# FPGA.net
KiCad netlist of a schematic drawn in Altium Designer
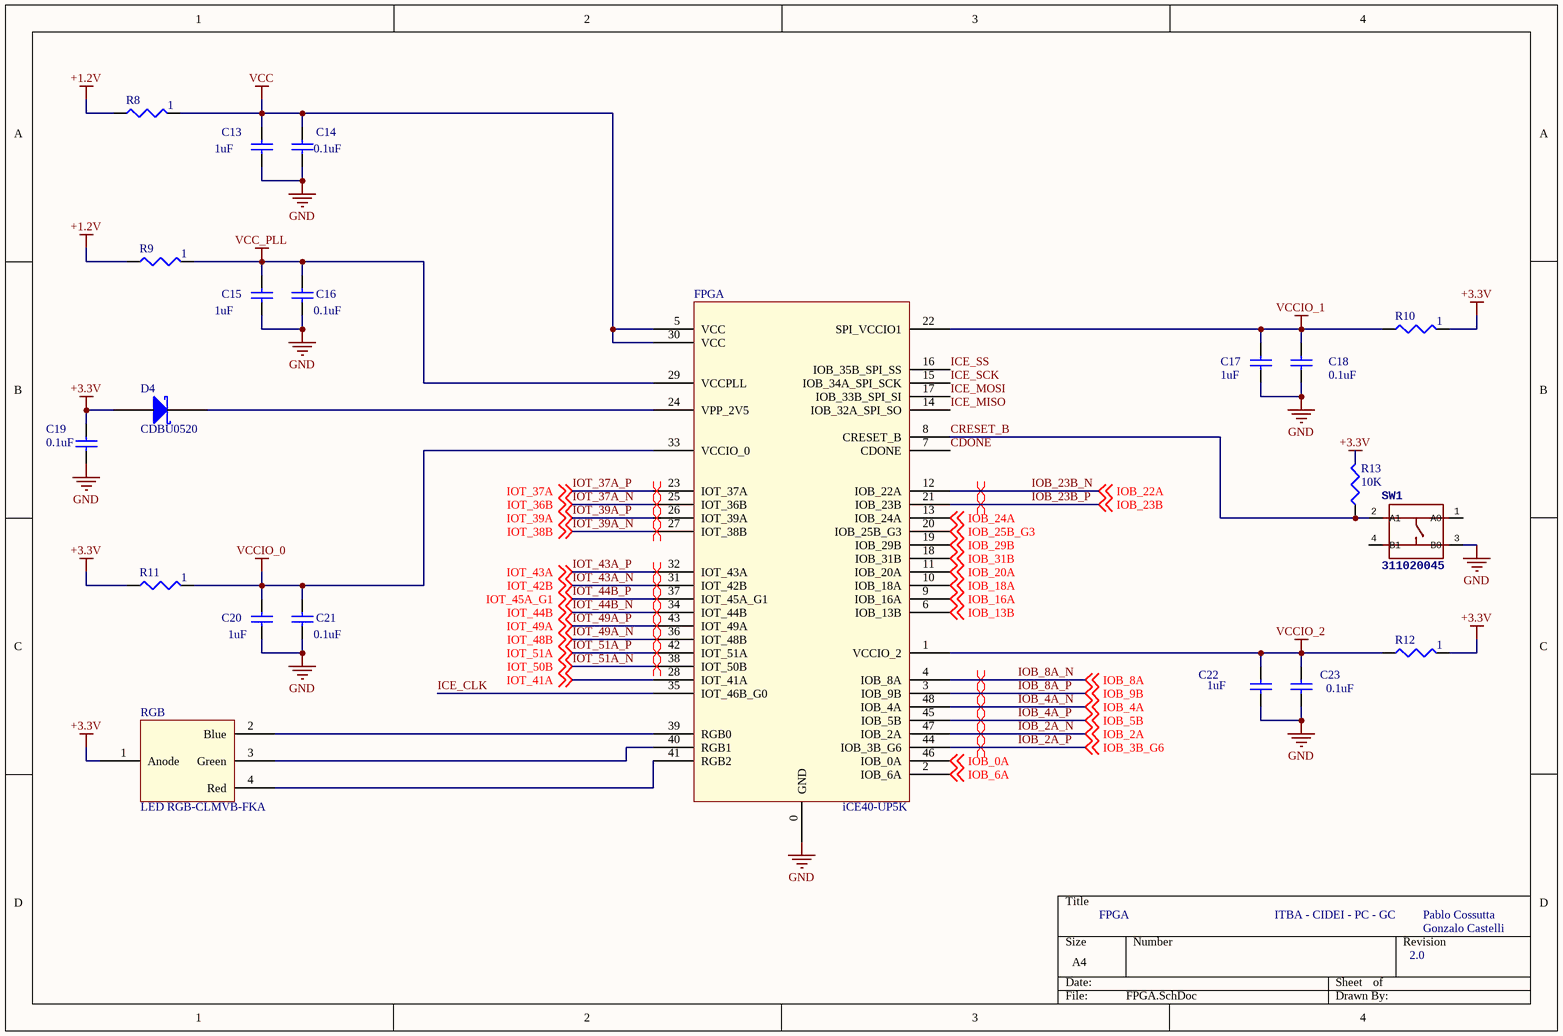
[diagram p0: FPGA.SchDoc]

(export (version "E")
  (design (tool "Eeschema 10.0.6"))
  (components
    (comp (ref "C13")
      (value "1uF")
      (footprint "C0402")
      (description "Capacitor (Semiconductor SIM Model)")
      (fields
        (field (name "MANUFACTURER") "TDK Corporation")
        (field (name "MANUFACTURER PART NUMBER") "CGB2A1JB1E105M033BC")
        (field (name "PUBLISHER") "Altium Limited")
      )
      (libsource (lib "Miscellaneous Devices") (part "Cap Semi"))
    )
    (comp (ref "C14")
      (value "0.1uF")
      (footprint "C0402")
      (description "Capacitor (Semiconductor SIM Model)")
      (fields
        (field (name "MANUFACTURER") "Samsung Electro-Mechanics")
        (field (name "MANUFACTURER PART NUMBER") "CL05B104KA5NNNC")
        (field (name "PUBLISHER") "Altium Limited")
      )
      (libsource (lib "Miscellaneous Devices") (part "Cap Semi"))
    )
    (comp (ref "C15")
      (value "1uF")
      (footprint "C0402")
      (description "Capacitor (Semiconductor SIM Model)")
      (fields
        (field (name "MANUFACTURER") "TDK Corporation")
        (field (name "MANUFACTURER PART NUMBER") "CGB2A1JB1E105M033BC")
        (field (name "PUBLISHER") "Altium Limited")
      )
      (libsource (lib "Miscellaneous Devices") (part "Cap Semi"))
    )
    (comp (ref "C16")
      (value "0.1uF")
      (footprint "C0402")
      (description "Capacitor (Semiconductor SIM Model)")
      (fields
        (field (name "MANUFACTURER") "Samsung Electro-Mechanics")
        (field (name "MANUFACTURER PART NUMBER") "CL05B104KA5NNNC")
        (field (name "PUBLISHER") "Altium Limited")
      )
      (libsource (lib "Miscellaneous Devices") (part "Cap Semi"))
    )
    (comp (ref "C17")
      (value "1uF")
      (footprint "C0402")
      (description "Capacitor (Semiconductor SIM Model)")
      (fields
        (field (name "MANUFACTURER") "TDK Corporation")
        (field (name "MANUFACTURER PART NUMBER") "CGB2A1JB1E105M033BC")
        (field (name "PUBLISHER") "Altium Limited")
      )
      (libsource (lib "Miscellaneous Devices") (part "Cap Semi"))
    )
    (comp (ref "C18")
      (value "0.1uF")
      (footprint "C0402")
      (description "Capacitor (Semiconductor SIM Model)")
      (fields
        (field (name "MANUFACTURER") "Samsung Electro-Mechanics")
        (field (name "MANUFACTURER PART NUMBER") "CL05B104KA5NNNC")
        (field (name "PUBLISHER") "Altium Limited")
      )
      (libsource (lib "Miscellaneous Devices") (part "Cap Semi"))
    )
    (comp (ref "C19")
      (value "0.1uF")
      (footprint "C0402")
      (description "Capacitor (Semiconductor SIM Model)")
      (fields
        (field (name "MANUFACTURER") "Samsung Electro-Mechanics")
        (field (name "MANUFACTURER PART NUMBER") "CL05B104KA5NNNC")
        (field (name "PUBLISHER") "Altium Limited")
      )
      (libsource (lib "Miscellaneous Devices") (part "Cap Semi"))
    )
    (comp (ref "C20")
      (value "1uF")
      (footprint "C0402")
      (description "Capacitor (Semiconductor SIM Model)")
      (fields
        (field (name "MANUFACTURER") "TDK Corporation")
        (field (name "MANUFACTURER PART NUMBER") "CGB2A1JB1E105M033BC")
        (field (name "PUBLISHER") "Altium Limited")
      )
      (libsource (lib "Miscellaneous Devices") (part "Cap Semi"))
    )
    (comp (ref "C21")
      (value "0.1uF")
      (footprint "C0402")
      (description "Capacitor (Semiconductor SIM Model)")
      (fields
        (field (name "MANUFACTURER") "Samsung Electro-Mechanics")
        (field (name "MANUFACTURER PART NUMBER") "CL05B104KA5NNNC")
        (field (name "PUBLISHER") "Altium Limited")
      )
      (libsource (lib "Miscellaneous Devices") (part "Cap Semi"))
    )
    (comp (ref "C22")
      (value "1uF")
      (footprint "C0402")
      (description "Capacitor (Semiconductor SIM Model)")
      (fields
        (field (name "MANUFACTURER") "TDK Corporation")
        (field (name "MANUFACTURER PART NUMBER") "CGB2A1JB1E105M033BC")
        (field (name "PUBLISHER") "Altium Limited")
      )
      (libsource (lib "Miscellaneous Devices") (part "Cap Semi"))
    )
    (comp (ref "C23")
      (value "0.1uF")
      (footprint "C0402")
      (description "Capacitor (Semiconductor SIM Model)")
      (fields
        (field (name "MANUFACTURER") "Samsung Electro-Mechanics")
        (field (name "MANUFACTURER PART NUMBER") "CL05B104KA5NNNC")
        (field (name "PUBLISHER") "Altium Limited")
      )
      (libsource (lib "Miscellaneous Devices") (part "Cap Semi"))
    )
    (comp (ref "D4")
      (value "CDBU0520")
      (footprint "CDBU0520")
      (description "DIODE SCHOTTKY 20V 500MA 0603")
      (fields (field (name "MANUFACTURER") "Comchip Technology"))
      (libsource (lib "FPGAlib") (part "CDBU0520"))
    )
    (comp (ref "FPGA")
      (value "iCE40-UP5K")
      (footprint "SLAB-QFN48-7X7-MD")
      (description "iCE40-UP5K FPGA")
      (fields
        (field (name "MANUFACTURER") "Lattice Semiconductor Corporation")
        (field (name "MANUFACTURER PART NUMBER") "ICE40UP5K-SG48ITR50")
      )
      (libsource (lib "FPGAlib") (part "iCE40-UP5K FPGA"))
    )
    (comp (ref "R8")
      (value "1")
      (footprint "R0402")
      (description "Resistor")
      (fields
        (field (name "MANUFACTURER") "Yageo")
        (field (name "MANUFACTURER PART NUMBER") "AC0402JR-071RL")
        (field (name "PUBLISHER") "Altium Limited")
      )
      (libsource (lib "Miscellaneous Devices") (part "Res3"))
    )
    (comp (ref "R9")
      (value "1")
      (footprint "R0402")
      (description "Resistor")
      (fields
        (field (name "MANUFACTURER") "Yageo")
        (field (name "MANUFACTURER PART NUMBER") "AC0402JR-071RL")
        (field (name "PUBLISHER") "Altium Limited")
      )
      (libsource (lib "Miscellaneous Devices") (part "Res3"))
    )
    (comp (ref "R10")
      (value "1")
      (footprint "R0402")
      (description "Resistor")
      (fields
        (field (name "MANUFACTURER") "Yageo")
        (field (name "MANUFACTURER PART NUMBER") "AC0402JR-071RL")
        (field (name "PUBLISHER") "Altium Limited")
      )
      (libsource (lib "Miscellaneous Devices") (part "Res3"))
    )
    (comp (ref "R11")
      (value "1")
      (footprint "R0402")
      (description "Resistor")
      (fields
        (field (name "MANUFACTURER") "Yageo")
        (field (name "MANUFACTURER PART NUMBER") "AC0402JR-071RL")
        (field (name "PUBLISHER") "Altium Limited")
      )
      (libsource (lib "Miscellaneous Devices") (part "Res3"))
    )
    (comp (ref "R12")
      (value "1")
      (footprint "R0402")
      (description "Resistor")
      (fields
        (field (name "MANUFACTURER") "Yageo")
        (field (name "MANUFACTURER PART NUMBER") "AC0402JR-071RL")
        (field (name "PUBLISHER") "Altium Limited")
      )
      (libsource (lib "Miscellaneous Devices") (part "Res3"))
    )
    (comp (ref "R13")
      (value "10K")
      (footprint "R0402")
      (description "Resistor")
      (fields
        (field (name "MANUFACTURER") "Yageo")
        (field (name "MANUFACTURER PART NUMBER") "RC0402JR-0710KP")
        (field (name "PUBLISHER") "Altium Limited")
      )
      (libsource (lib "Miscellaneous Devices") (part "Res3"))
    )
    (comp (ref "RGB")
      (value "LED RGB-CLMVB-FKA")
      (footprint "ledRGB")
      (description "LED RGB CLEAR 4PLCC SMD")
      (fields
        (field (name "MANUFACTURER") "Cree Inc.")
        (field (name "MANUFACTURER PART NUMBER") "CLMVC-FKA-CL1D1L71BB7C3C3")
      )
      (libsource (lib "FPGAlib") (part "LED RGB-CLMVB-FKA"))
    )
    (comp (ref "SW1")
      (value "311020045")
      (footprint "SW4-SMD-4.2X3.2X2.5MM")
      (description "SWITCH TACTILE SPST-NO 0.05A 16V")
      (fields (field (name "MPN") "DHT-4235A") (field (name "MANUFACTURER") "C&K"))
      (libsource (lib "FPGAlib") (part "PTS810 SJM 250 SMTR LFS"))
    )
  )
  (nets
    (net (code "1") (name "+1.2V") (class "Default")
      (node (ref "R8") (pin "1") (pinfunction "1_1") (pintype "passive"))
      (node (ref "R9") (pin "1") (pinfunction "1_1") (pintype "passive"))
    )
    (net (code "2") (name "+3.3V") (class "Default")
      (node (ref "C19") (pin "2") (pinfunction "2_2") (pintype "passive"))
      (node (ref "D4") (pin "1") (pintype "passive"))
      (node (ref "R10") (pin "2") (pinfunction "2_2") (pintype "passive"))
      (node (ref "R11") (pin "1") (pinfunction "1_1") (pintype "passive"))
      (node (ref "R12") (pin "2") (pinfunction "2_2") (pintype "passive"))
      (node (ref "R13") (pin "2") (pinfunction "2_2") (pintype "passive"))
      (node (ref "RGB") (pin "1") (pinfunction "Anode_1") (pintype "passive"))
    )
    (net (code "3") (name "/CDONE") (class "Default")
      (node (ref "FPGA") (pin "7") (pinfunction "CDONE_7") (pintype "passive"))
    )
    (net (code "4") (name "/CRESET_B") (class "Default")
      (node (ref "FPGA") (pin "8") (pinfunction "CRESET_B_8") (pintype "passive"))
      (node (ref "R13") (pin "1") (pinfunction "1_1") (pintype "passive"))
      (node (ref "SW1") (pin "2") (pinfunction "A1_2") (pintype "passive"))
    )
    (net (code "5") (name "/ICE_CLK") (class "Default")
      (node (ref "FPGA") (pin "35") (pinfunction "IOT_46B_G0_35") (pintype "passive"))
    )
    (net (code "6") (name "/ICE_MISO") (class "Default")
      (node (ref "FPGA") (pin "14") (pinfunction "IOB_32A_SPI_SO_14") (pintype "passive"))
    )
    (net (code "7") (name "/ICE_MOSI") (class "Default")
      (node (ref "FPGA") (pin "17") (pinfunction "IOB_33B_SPI_SI_17") (pintype "passive"))
    )
    (net (code "8") (name "/ICE_SCK") (class "Default")
      (node (ref "FPGA") (pin "15") (pinfunction "IOB_34A_SPI_SCK_15") (pintype "passive"))
    )
    (net (code "9") (name "/ICE_SS") (class "Default")
      (node (ref "FPGA") (pin "16") (pinfunction "IOB_35B_SPI_SS_16") (pintype "passive"))
    )
    (net (code "10") (name "GND") (class "Default")
      (node (ref "C13") (pin "1") (pinfunction "1_1") (pintype "passive"))
      (node (ref "C14") (pin "1") (pinfunction "1_1") (pintype "passive"))
      (node (ref "C15") (pin "1") (pinfunction "1_1") (pintype "passive"))
      (node (ref "C16") (pin "1") (pinfunction "1_1") (pintype "passive"))
      (node (ref "C17") (pin "1") (pinfunction "1_1") (pintype "passive"))
      (node (ref "C18") (pin "1") (pinfunction "1_1") (pintype "passive"))
      (node (ref "C19") (pin "1") (pinfunction "1_1") (pintype "passive"))
      (node (ref "C20") (pin "1") (pinfunction "1_1") (pintype "passive"))
      (node (ref "C21") (pin "1") (pinfunction "1_1") (pintype "passive"))
      (node (ref "C22") (pin "1") (pinfunction "1_1") (pintype "passive"))
      (node (ref "C23") (pin "1") (pinfunction "1_1") (pintype "passive"))
      (node (ref "FPGA") (pin "0") (pinfunction "GND_0") (pintype "passive"))
      (node (ref "SW1") (pin "3") (pinfunction "B0_3") (pintype "passive"))
    )
    (net (code "11") (name "IOB_0A") (class "Default")
      (node (ref "FPGA") (pin "46") (pinfunction "IOB_0A_46") (pintype "passive"))
    )
    (net (code "12") (name "IOB_2A") (class "Default")
      (node (ref "FPGA") (pin "47") (pinfunction "IOB_2A_47") (pintype "passive"))
    )
    (net (code "13") (name "IOB_3B_G6") (class "Default")
      (node (ref "FPGA") (pin "44") (pinfunction "IOB_3B_G6_44") (pintype "passive"))
    )
    (net (code "14") (name "IOB_4A") (class "Default")
      (node (ref "FPGA") (pin "48") (pinfunction "IOB_4A_48") (pintype "passive"))
    )
    (net (code "15") (name "IOB_5B") (class "Default")
      (node (ref "FPGA") (pin "45") (pinfunction "IOB_5B_45") (pintype "passive"))
    )
    (net (code "16") (name "IOB_6A") (class "Default")
      (node (ref "FPGA") (pin "2") (pinfunction "IOB_6A_2") (pintype "passive"))
    )
    (net (code "17") (name "IOB_8A") (class "Default")
      (node (ref "FPGA") (pin "4") (pinfunction "IOB_8A_4") (pintype "passive"))
    )
    (net (code "18") (name "IOB_9B") (class "Default")
      (node (ref "FPGA") (pin "3") (pinfunction "IOB_9B_3") (pintype "passive"))
    )
    (net (code "19") (name "IOB_13B") (class "Default")
      (node (ref "FPGA") (pin "6") (pinfunction "IOB_13B_6") (pintype "passive"))
    )
    (net (code "20") (name "IOB_16A") (class "Default")
      (node (ref "FPGA") (pin "9") (pinfunction "IOB_16A_9") (pintype "passive"))
    )
    (net (code "21") (name "IOB_18A") (class "Default")
      (node (ref "FPGA") (pin "10") (pinfunction "IOB_18A_10") (pintype "passive"))
    )
    (net (code "22") (name "IOB_20A") (class "Default")
      (node (ref "FPGA") (pin "11") (pinfunction "IOB_20A_11") (pintype "passive"))
    )
    (net (code "23") (name "IOB_22A") (class "Default")
      (node (ref "FPGA") (pin "12") (pinfunction "IOB_22A_12") (pintype "passive"))
    )
    (net (code "24") (name "IOB_23B") (class "Default")
      (node (ref "FPGA") (pin "21") (pinfunction "IOB_23B_21") (pintype "passive"))
    )
    (net (code "25") (name "IOB_24A") (class "Default")
      (node (ref "FPGA") (pin "13") (pinfunction "IOB_24A_13") (pintype "passive"))
    )
    (net (code "26") (name "IOB_25B_G3") (class "Default")
      (node (ref "FPGA") (pin "20") (pinfunction "IOB_25B_G3_20") (pintype "passive"))
    )
    (net (code "27") (name "IOB_29B") (class "Default")
      (node (ref "FPGA") (pin "19") (pinfunction "IOB_29B_19") (pintype "passive"))
    )
    (net (code "28") (name "IOB_31B") (class "Default")
      (node (ref "FPGA") (pin "18") (pinfunction "IOB_31B_18") (pintype "passive"))
    )
    (net (code "29") (name "IOT_36B") (class "Default")
      (node (ref "FPGA") (pin "25") (pinfunction "IOT_36B_25") (pintype "passive"))
    )
    (net (code "30") (name "IOT_37A") (class "Default")
      (node (ref "FPGA") (pin "23") (pinfunction "IOT_37A_23") (pintype "passive"))
    )
    (net (code "31") (name "IOT_38B") (class "Default")
      (node (ref "FPGA") (pin "27") (pinfunction "IOT_38B_27") (pintype "passive"))
    )
    (net (code "32") (name "IOT_39A") (class "Default")
      (node (ref "FPGA") (pin "26") (pinfunction "IOT_39A_26") (pintype "passive"))
    )
    (net (code "33") (name "IOT_41A") (class "Default")
      (node (ref "FPGA") (pin "28") (pinfunction "IOT_41A_28") (pintype "passive"))
    )
    (net (code "34") (name "IOT_42B") (class "Default")
      (node (ref "FPGA") (pin "31") (pinfunction "IOT_42B_31") (pintype "passive"))
    )
    (net (code "35") (name "IOT_43A") (class "Default")
      (node (ref "FPGA") (pin "32") (pinfunction "IOT_43A_32") (pintype "passive"))
    )
    (net (code "36") (name "IOT_44B") (class "Default")
      (node (ref "FPGA") (pin "34") (pinfunction "IOT_44B_34") (pintype "passive"))
    )
    (net (code "37") (name "IOT_45A_G1") (class "Default")
      (node (ref "FPGA") (pin "37") (pinfunction "IOT_45A_G1_37") (pintype "passive"))
    )
    (net (code "38") (name "IOT_48B") (class "Default")
      (node (ref "FPGA") (pin "36") (pinfunction "IOT_48B_36") (pintype "passive"))
    )
    (net (code "39") (name "IOT_49A") (class "Default")
      (node (ref "FPGA") (pin "43") (pinfunction "IOT_49A_43") (pintype "passive"))
    )
    (net (code "40") (name "IOT_50B") (class "Default")
      (node (ref "FPGA") (pin "38") (pinfunction "IOT_50B_38") (pintype "passive"))
    )
    (net (code "41") (name "IOT_51A") (class "Default")
      (node (ref "FPGA") (pin "42") (pinfunction "IOT_51A_42") (pintype "passive"))
    )
    (net (code "42") (name "Net-(FPGA-RGB0)") (class "Default")
      (node (ref "FPGA") (pin "39") (pinfunction "RGB0_39") (pintype "passive"))
      (node (ref "RGB") (pin "2") (pinfunction "Blue_2") (pintype "passive"))
    )
    (net (code "43") (name "Net-(FPGA-RGB1)") (class "Default")
      (node (ref "FPGA") (pin "40") (pinfunction "RGB1_40") (pintype "passive"))
      (node (ref "RGB") (pin "3") (pinfunction "Green_3") (pintype "passive"))
    )
    (net (code "44") (name "Net-(FPGA-RGB2)") (class "Default")
      (node (ref "FPGA") (pin "41") (pinfunction "RGB2_41") (pintype "passive"))
      (node (ref "RGB") (pin "4") (pinfunction "Red_4") (pintype "passive"))
    )
    (net (code "45") (name "Net-(FPGA-VPP_2V5)") (class "Default")
      (node (ref "D4") (pin "2") (pintype "passive"))
      (node (ref "FPGA") (pin "24") (pinfunction "VPP_2V5_24") (pintype "passive"))
    )
    (net (code "46") (name "VCC") (class "Default")
      (node (ref "C13") (pin "2") (pinfunction "2_2") (pintype "passive"))
      (node (ref "C14") (pin "2") (pinfunction "2_2") (pintype "passive"))
      (node (ref "FPGA") (pin "30") (pinfunction "VCC_30") (pintype "passive"))
      (node (ref "FPGA") (pin "5") (pinfunction "VCC_5") (pintype "passive"))
      (node (ref "R8") (pin "2") (pinfunction "2_2") (pintype "passive"))
    )
    (net (code "47") (name "VCCIO_0") (class "Default")
      (node (ref "C20") (pin "2") (pinfunction "2_2") (pintype "passive"))
      (node (ref "C21") (pin "2") (pinfunction "2_2") (pintype "passive"))
      (node (ref "FPGA") (pin "33") (pinfunction "VCCIO_0_33") (pintype "passive"))
      (node (ref "R11") (pin "2") (pinfunction "2_2") (pintype "passive"))
    )
    (net (code "48") (name "VCCIO_1") (class "Default")
      (node (ref "C17") (pin "2") (pinfunction "2_2") (pintype "passive"))
      (node (ref "C18") (pin "2") (pinfunction "2_2") (pintype "passive"))
      (node (ref "FPGA") (pin "22") (pinfunction "SPI_VCCIO1_22") (pintype "passive"))
      (node (ref "R10") (pin "1") (pinfunction "1_1") (pintype "passive"))
    )
    (net (code "49") (name "VCCIO_2") (class "Default")
      (node (ref "C22") (pin "2") (pinfunction "2_2") (pintype "passive"))
      (node (ref "C23") (pin "2") (pinfunction "2_2") (pintype "passive"))
      (node (ref "FPGA") (pin "1") (pinfunction "VCCIO_2_1") (pintype "passive"))
      (node (ref "R12") (pin "1") (pinfunction "1_1") (pintype "passive"))
    )
    (net (code "50") (name "VCC_PLL") (class "Default")
      (node (ref "C15") (pin "2") (pinfunction "2_2") (pintype "passive"))
      (node (ref "C16") (pin "2") (pinfunction "2_2") (pintype "passive"))
      (node (ref "FPGA") (pin "29") (pinfunction "VCCPLL_29") (pintype "passive"))
      (node (ref "R9") (pin "2") (pinfunction "2_2") (pintype "passive"))
    )
    (net (code "51") (name "unconnected-(SW1-A0-Pad1)") (class "Default")
      (node (ref "SW1") (pin "1") (pinfunction "A0_1") (pintype "passive"))
    )
    (net (code "52") (name "unconnected-(SW1-B1-Pad4)") (class "Default")
      (node (ref "SW1") (pin "4") (pinfunction "B1_4") (pintype "passive"))
    )
  )
)
